# NoteIt.net
KiCad netlist of a schematic drawn in EAGLE
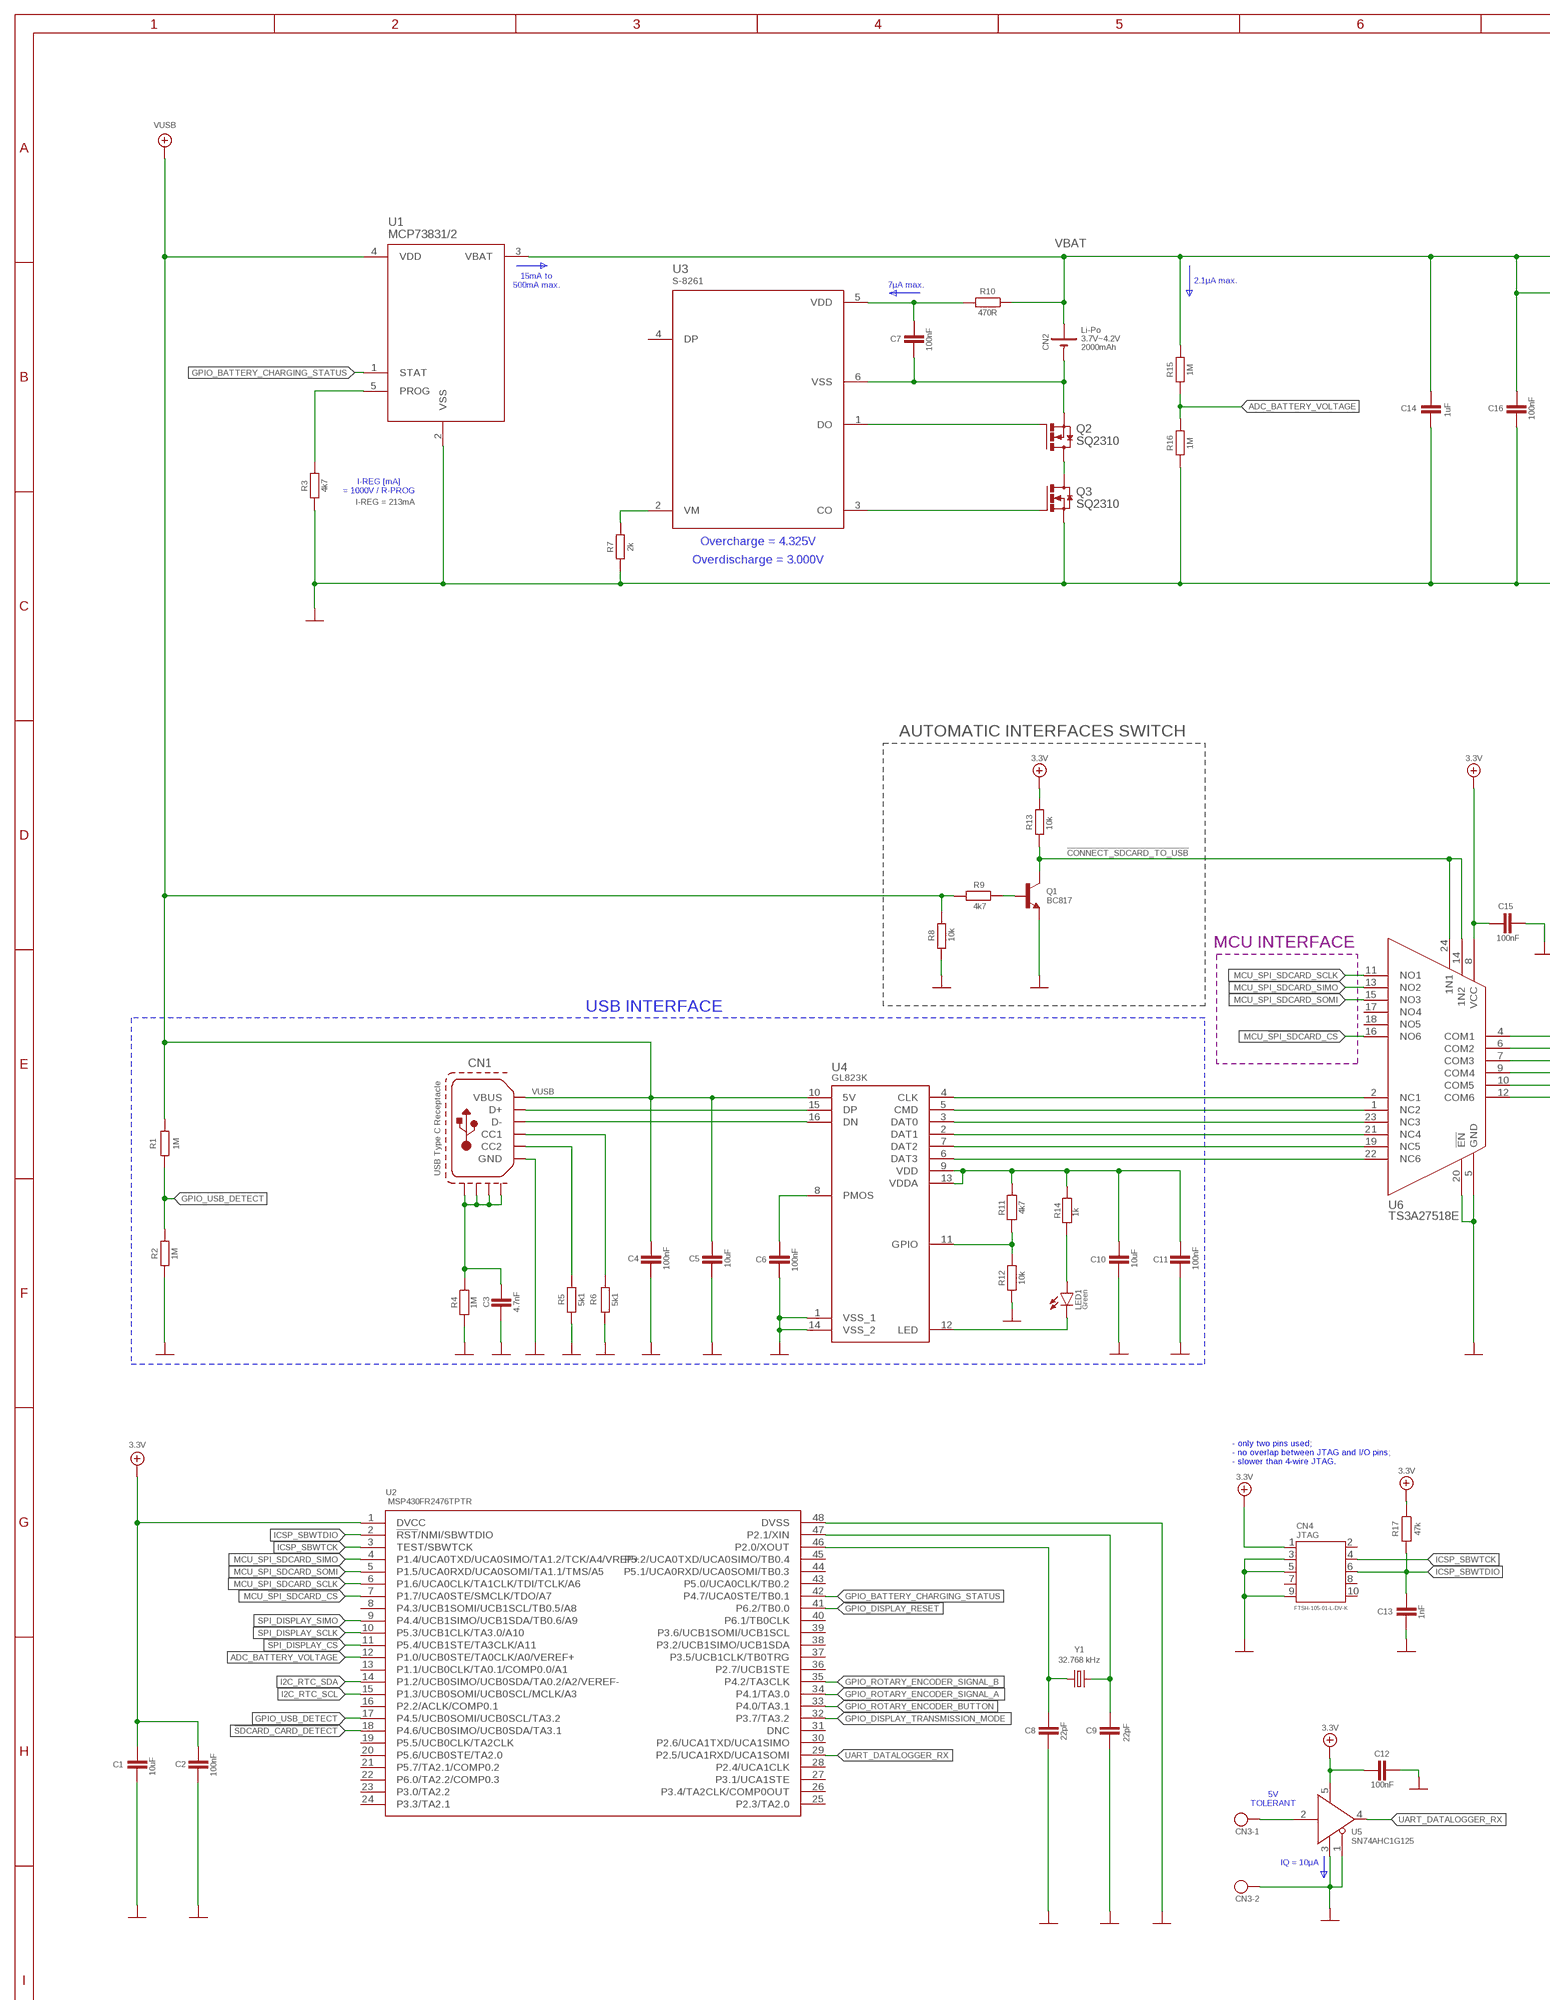
[diagram p0: schematic, sheet 1, part 1 of 2]
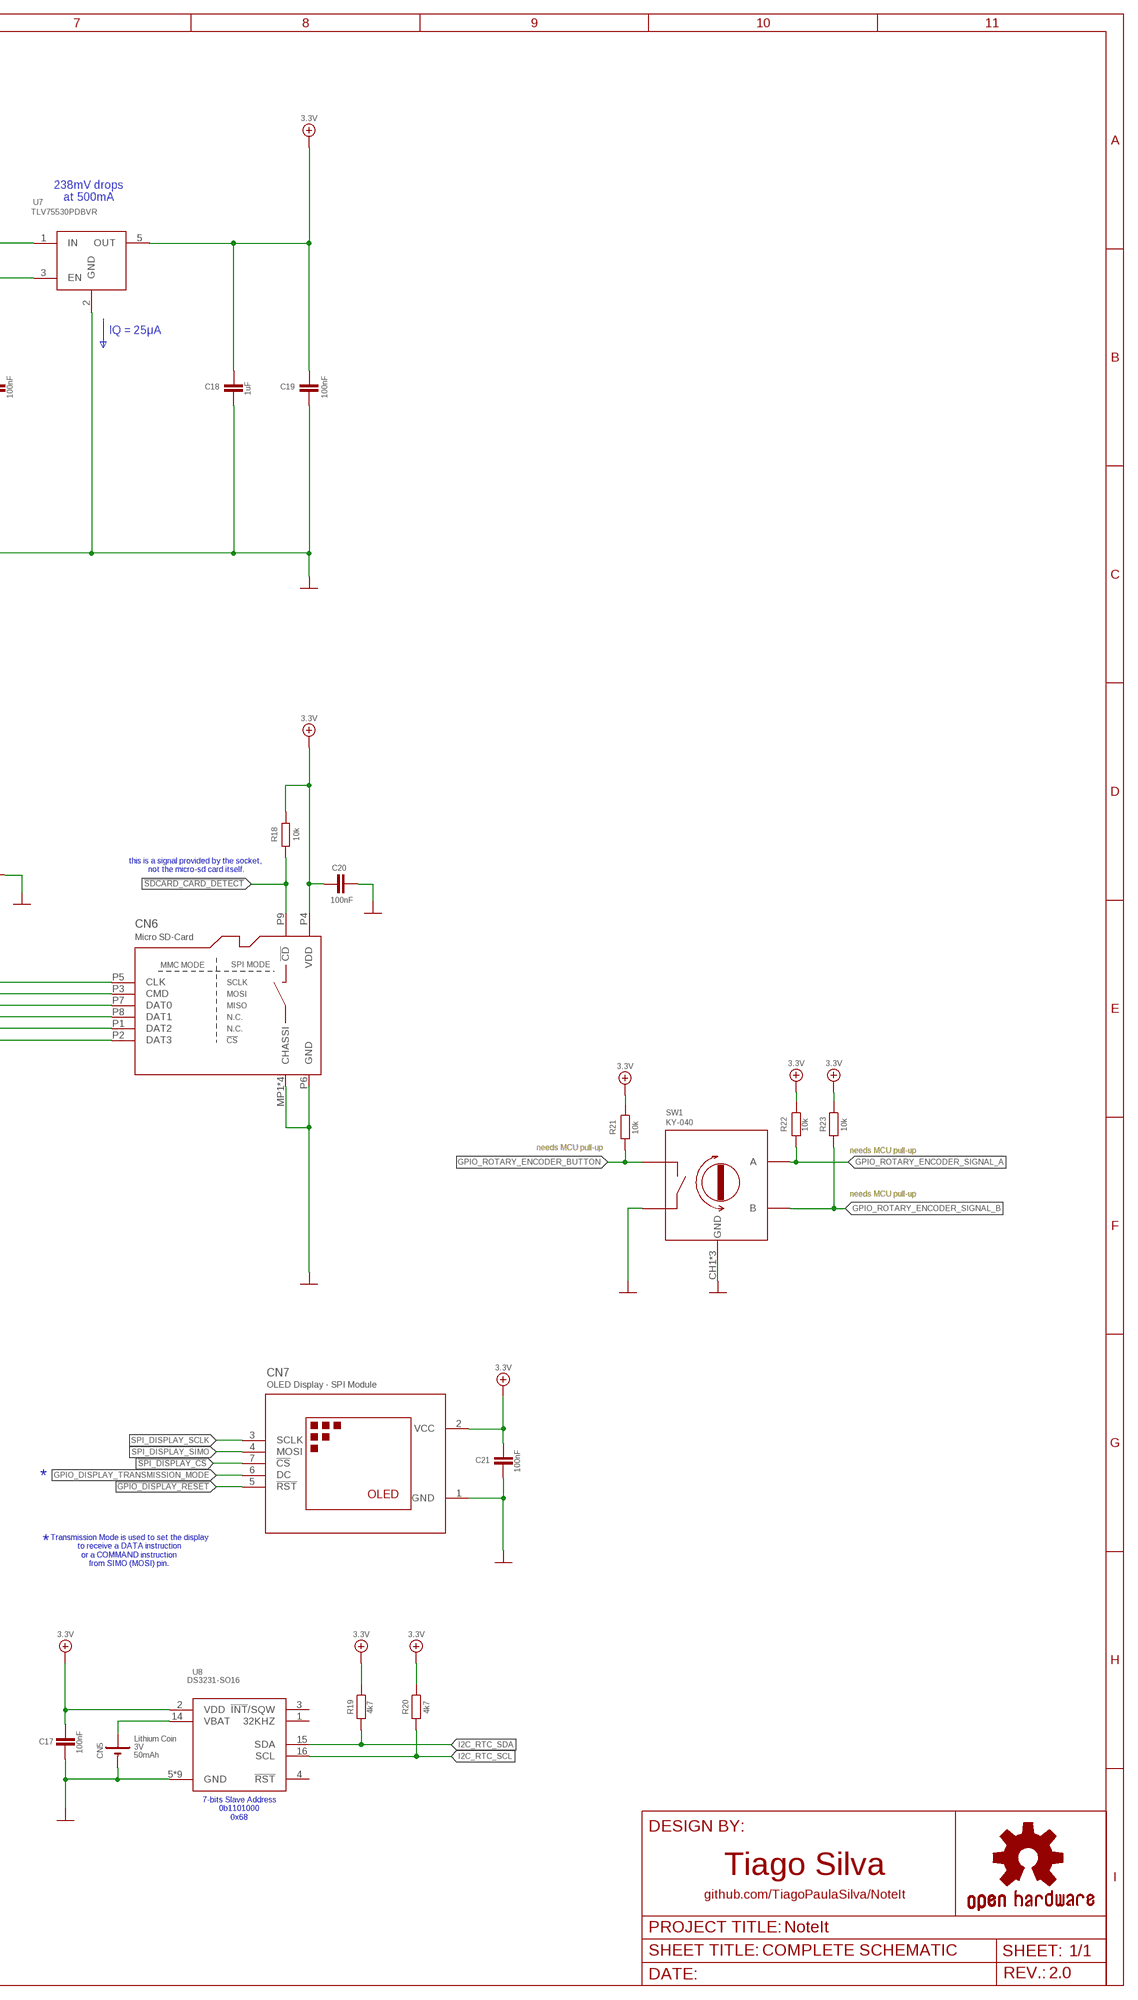
[diagram p1: schematic, sheet 1, part 2 of 2]

(export (version "E")
  (design (tool "Eeschema 10.0.6"))
  (components
    (comp (ref "C1")
      (value "10uF")
      (footprint "eagle-import:C0603")
      (libsource (lib "eagle-import") (part "C_0603"))
    )
    (comp (ref "C2")
      (value "100nF")
      (footprint "eagle-import:C0603")
      (libsource (lib "eagle-import") (part "C_0603"))
    )
    (comp (ref "C3")
      (value "4.7nF")
      (footprint "eagle-import:C0603")
      (libsource (lib "eagle-import") (part "C_0603"))
    )
    (comp (ref "C4")
      (value "100nF")
      (footprint "eagle-import:C0603")
      (libsource (lib "eagle-import") (part "C_0603"))
    )
    (comp (ref "C5")
      (value "10uF")
      (footprint "eagle-import:C0603")
      (libsource (lib "eagle-import") (part "C_0603"))
    )
    (comp (ref "C6")
      (value "100nF")
      (footprint "eagle-import:C0603")
      (libsource (lib "eagle-import") (part "C_0603"))
    )
    (comp (ref "C7")
      (value "100nF")
      (footprint "eagle-import:C0603")
      (libsource (lib "eagle-import") (part "C_0603"))
    )
    (comp (ref "C8")
      (value "22pF")
      (footprint "eagle-import:C0603")
      (libsource (lib "eagle-import") (part "C_0603"))
    )
    (comp (ref "C9")
      (value "22pF")
      (footprint "eagle-import:C0603")
      (libsource (lib "eagle-import") (part "C_0603"))
    )
    (comp (ref "C10")
      (value "10uF")
      (footprint "eagle-import:C0603")
      (libsource (lib "eagle-import") (part "C_0603"))
    )
    (comp (ref "C11")
      (value "100nF")
      (footprint "eagle-import:C0603")
      (libsource (lib "eagle-import") (part "C_0603"))
    )
    (comp (ref "C12")
      (value "100nF")
      (footprint "eagle-import:C0603")
      (libsource (lib "eagle-import") (part "C_0603"))
    )
    (comp (ref "C13")
      (value "1nF")
      (footprint "eagle-import:C0603")
      (libsource (lib "eagle-import") (part "C_0603"))
    )
    (comp (ref "C14")
      (value "1uF")
      (footprint "eagle-import:C0603")
      (libsource (lib "eagle-import") (part "C_0603"))
    )
    (comp (ref "C15")
      (value "100nF")
      (footprint "eagle-import:C0603")
      (libsource (lib "eagle-import") (part "C_0603"))
    )
    (comp (ref "C16")
      (value "100nF")
      (footprint "eagle-import:C0603")
      (libsource (lib "eagle-import") (part "C_0603"))
    )
    (comp (ref "C17")
      (value "100nF")
      (footprint "eagle-import:C0603")
      (libsource (lib "eagle-import") (part "C_0603"))
    )
    (comp (ref "C18")
      (value "1uF")
      (footprint "eagle-import:C0603")
      (libsource (lib "eagle-import") (part "C_0603"))
    )
    (comp (ref "C19")
      (value "100nF")
      (footprint "eagle-import:C0603")
      (libsource (lib "eagle-import") (part "C_0603"))
    )
    (comp (ref "C20")
      (value "100nF")
      (footprint "eagle-import:C0603")
      (libsource (lib "eagle-import") (part "C_0603"))
    )
    (comp (ref "C21")
      (value "100nF")
      (footprint "eagle-import:C0603")
      (libsource (lib "eagle-import") (part "C_0603"))
    )
    (comp (ref "CN1")
      (value "USB Type C Receptacle")
      (footprint "eagle-import:USB-C-16P-2LAYER-PADS")
      (libsource (lib "eagle-import") (part "USB-C-16P-2LAYERS"))
    )
    (comp (ref "CN2")
      (value "CELL-JST-PH-2P-H")
      (footprint "eagle-import:JST-PH-2P-H")
      (fields
        (field (name "CAPACITY") "2000mAh")
        (field (name "TYPE") "Li-Po")
        (field (name "VOLTAGE") "3.7V~4.2V")
      )
      (libsource (lib "eagle-import") (part "CELL-JST-PH-2P-H"))
    )
    (comp (ref "CN3")
      (value "2P-BLOCK-3.5MM-2P")
      (footprint "eagle-import:BLOCK-3.5MM-2P")
      (libsource (lib "eagle-import") (part "2P-BLOCK-3.5MM-2P"))
    )
    (comp (ref "CN4")
      (value "JTAG")
      (footprint "eagle-import:JTAG-ARM-10P")
      (fields (field (name "PN") "FTSH-105-01-L-DV-K"))
      (libsource (lib "eagle-import") (part "JTAG"))
    )
    (comp (ref "CN5")
      (value "CR-1225")
      (footprint "eagle-import:CR1220_1225_HOLDER")
      (fields
        (field (name "TYPE") "Lithium Coin")
        (field (name "VOLTAGE") "3V")
        (field (name "CAPACITY") "50mAh")
      )
      (libsource (lib "eagle-import") (part "CR-1225"))
    )
    (comp (ref "CN6")
      (value "Micro SD-Card")
      (footprint "eagle-import:SD-CARD")
      (libsource (lib "eagle-import") (part "SD-CARD"))
    )
    (comp (ref "CN7")
      (value "OLED-MODULE-SPI-NO_HOLES")
      (footprint "eagle-import:PIN_HEADER_1X7_NH")
      (fields (field (name "FAMILY") "OLED Display - SPI Module"))
      (libsource (lib "eagle-import") (part "OLED-MODULE-SPI-NO_HOLES"))
    )
    (comp (ref "LED1")
      (value "LED-0603")
      (footprint "eagle-import:LED-0603")
      (fields (field (name "FAMILY") "Green"))
      (libsource (lib "eagle-import") (part "LED-0603"))
    )
    (comp (ref "Q1")
      (value "BC817")
      (footprint "eagle-import:SOT23-3")
      (libsource (lib "eagle-import") (part "NPN-BC817"))
    )
    (comp (ref "Q2")
      (value "N-FET-ENHANCEMENT-SQ2310")
      (footprint "eagle-import:SOT23-3")
      (fields (field (name "FAMILY") "SQ2310"))
      (libsource (lib "eagle-import") (part "N-FET-ENHANCEMENT-SQ2310"))
    )
    (comp (ref "Q3")
      (value "N-FET-ENHANCEMENT-SQ2310")
      (footprint "eagle-import:SOT23-3")
      (fields (field (name "FAMILY") "SQ2310"))
      (libsource (lib "eagle-import") (part "N-FET-ENHANCEMENT-SQ2310"))
    )
    (comp (ref "R1")
      (value "1M")
      (footprint "eagle-import:R0603")
      (libsource (lib "eagle-import") (part "R_0603"))
    )
    (comp (ref "R2")
      (value "1M")
      (footprint "eagle-import:R0603")
      (libsource (lib "eagle-import") (part "R_0603"))
    )
    (comp (ref "R3")
      (value "4k7")
      (footprint "eagle-import:R0603")
      (libsource (lib "eagle-import") (part "R_0603"))
    )
    (comp (ref "R4")
      (value "1M")
      (footprint "eagle-import:R0603")
      (libsource (lib "eagle-import") (part "R_0603"))
    )
    (comp (ref "R5")
      (value "5k1")
      (footprint "eagle-import:R0603")
      (libsource (lib "eagle-import") (part "R_0603"))
    )
    (comp (ref "R6")
      (value "5k1")
      (footprint "eagle-import:R0603")
      (libsource (lib "eagle-import") (part "R_0603"))
    )
    (comp (ref "R7")
      (value "2k")
      (footprint "eagle-import:R0603")
      (libsource (lib "eagle-import") (part "R_0603"))
    )
    (comp (ref "R8")
      (value "10k")
      (footprint "eagle-import:R0603")
      (libsource (lib "eagle-import") (part "R_0603"))
    )
    (comp (ref "R9")
      (value "4k7")
      (footprint "eagle-import:R0603")
      (libsource (lib "eagle-import") (part "R_0603"))
    )
    (comp (ref "R10")
      (value "470R")
      (footprint "eagle-import:R0603")
      (libsource (lib "eagle-import") (part "R_0603"))
    )
    (comp (ref "R11")
      (value "4k7")
      (footprint "eagle-import:R0603")
      (libsource (lib "eagle-import") (part "R_0603"))
    )
    (comp (ref "R12")
      (value "10k")
      (footprint "eagle-import:R0603")
      (libsource (lib "eagle-import") (part "R_0603"))
    )
    (comp (ref "R13")
      (value "10k")
      (footprint "eagle-import:R0603")
      (libsource (lib "eagle-import") (part "R_0603"))
    )
    (comp (ref "R14")
      (value "1k")
      (footprint "eagle-import:R0603")
      (libsource (lib "eagle-import") (part "R_0603"))
    )
    (comp (ref "R15")
      (value "1M")
      (footprint "eagle-import:R0603")
      (libsource (lib "eagle-import") (part "R_0603"))
    )
    (comp (ref "R16")
      (value "1M")
      (footprint "eagle-import:R0603")
      (libsource (lib "eagle-import") (part "R_0603"))
    )
    (comp (ref "R17")
      (value "47k")
      (footprint "eagle-import:R0603")
      (libsource (lib "eagle-import") (part "R_0603"))
    )
    (comp (ref "R18")
      (value "10k")
      (footprint "eagle-import:R0603")
      (libsource (lib "eagle-import") (part "R_0603"))
    )
    (comp (ref "R19")
      (value "4k7")
      (footprint "eagle-import:R0603")
      (libsource (lib "eagle-import") (part "R_0603"))
    )
    (comp (ref "R20")
      (value "4k7")
      (footprint "eagle-import:R0603")
      (libsource (lib "eagle-import") (part "R_0603"))
    )
    (comp (ref "R21")
      (value "10k")
      (footprint "eagle-import:R0603")
      (libsource (lib "eagle-import") (part "R_0603"))
    )
    (comp (ref "R22")
      (value "10k")
      (footprint "eagle-import:R0603")
      (libsource (lib "eagle-import") (part "R_0603"))
    )
    (comp (ref "R23")
      (value "10k")
      (footprint "eagle-import:R0603")
      (libsource (lib "eagle-import") (part "R_0603"))
    )
    (comp (ref "SW1")
      (value "KY-040")
      (footprint "eagle-import:KY-040")
      (libsource (lib "eagle-import") (part "ROTARY-ENCODER"))
    )
    (comp (ref "U1")
      (value "MCP73831/2")
      (footprint "eagle-import:SOT-23-5")
      (libsource (lib "eagle-import") (part "MCP73831T-2ACI/OT"))
    )
    (comp (ref "U2")
      (value "MSP430FR2476TPTR")
      (footprint "eagle-import:LQFP-48")
      (fields
        (field (name "MOUSER_PART_NUMBER") "595-MSP430FR2476TPTR")
        (field (name "PN") "MSP430FR2476TPTR")
      )
      (libsource (lib "eagle-import") (part "MSP430FR2476TPTR"))
    )
    (comp (ref "U3")
      (value "S-8261")
      (footprint "eagle-import:SOT-23-6")
      (fields (field (name "SPICEPREFIX") "X"))
      (libsource (lib "eagle-import") (part "S-8261"))
    )
    (comp (ref "U4")
      (value "GL823K")
      (footprint "eagle-import:SSOP16")
      (libsource (lib "eagle-import") (part "GL823K"))
    )
    (comp (ref "U5")
      (value "SN74AHC1G125")
      (footprint "eagle-import:SOT-23-5")
      (libsource (lib "eagle-import") (part "SN74AHC1G125"))
    )
    (comp (ref "U6")
      (value "TS3A27518E")
      (footprint "eagle-import:TSSOP-24")
      (libsource (lib "eagle-import") (part "TS3A27518E"))
    )
    (comp (ref "U7")
      (value "TLV75530PDBVR")
      (footprint "eagle-import:SOT-23-5")
      (libsource (lib "eagle-import") (part "TLV75530PDBVR"))
    )
    (comp (ref "U8")
      (value "DS3231-SO16")
      (footprint "eagle-import:SOIC-16W_(SO16)")
      (libsource (lib "eagle-import") (part "DS3231-SO16"))
    )
    (comp (ref "Y1")
      (value "32.768 kHz")
      (footprint "eagle-import:3.2MM_1.6MM")
      (fields (field (name "PN") "CM7V-T1A-32.768k-9pF-20PPM-TA-QA T3"))
      (libsource (lib "eagle-import") (part "OSC-32.768KHZ"))
    )
  )
  (nets
    (net (code "1") (name "/MCU_~{SPI_SDCARD_CS}") (class "Default")
      (node (ref "U2") (pin "7") (pinfunction "P1.7/UCA0STE/SMCLK/TDO/A7_7") (pintype "bidirectional"))
      (node (ref "U6") (pin "16") (pinfunction "NO6_16") (pintype "bidirectional"))
    )
    (net (code "2") (name "/VBAT") (class "Default")
      (node (ref "C14") (pin "1") (pinfunction "1_1") (pintype "passive"))
      (node (ref "C16") (pin "1") (pinfunction "1_1") (pintype "passive"))
      (node (ref "CN2") (pin "1") (pinfunction "+_1") (pintype "passive"))
      (node (ref "R10") (pin "1") (pinfunction "1_1") (pintype "passive"))
      (node (ref "R15") (pin "2") (pinfunction "2_2") (pintype "passive"))
      (node (ref "U1") (pin "3") (pinfunction "VBAT_3") (pintype "bidirectional"))
      (node (ref "U7") (pin "1") (pinfunction "IN_1") (pintype "bidirectional"))
      (node (ref "U7") (pin "3") (pinfunction "EN_3") (pintype "bidirectional"))
    )
    (net (code "3") (name "/~{CONNECT_SDCARD_TO_USB}") (class "Default")
      (node (ref "Q1") (pin "3") (pinfunction "C_3") (pintype "passive"))
      (node (ref "R13") (pin "1") (pinfunction "1_1") (pintype "passive"))
      (node (ref "U6") (pin "14") (pinfunction "1N2_14") (pintype "input"))
      (node (ref "U6") (pin "24") (pinfunction "1N1_24") (pintype "input"))
    )
    (net (code "4") (name "/~{GPIO_DISPLAY_RESET}") (class "Default")
      (node (ref "CN7") (pin "5") (pinfunction "~{RST}_5") (pintype "bidirectional"))
      (node (ref "U2") (pin "41") (pinfunction "P6.2/TB0.0_41") (pintype "bidirectional"))
    )
    (net (code "5") (name "/~{SDCARD_CARD_DETECT}") (class "Default")
      (node (ref "CN6") (pin "P9") (pinfunction "~{CD}_P9") (pintype "bidirectional"))
      (node (ref "R18") (pin "2") (pinfunction "2_2") (pintype "passive"))
      (node (ref "U2") (pin "18") (pinfunction "P4.6/UCB0SIMO/UCB0SDA/TA3.1_18") (pintype "bidirectional"))
    )
    (net (code "6") (name "/~{SPI_DISPLAY_CS}") (class "Default")
      (node (ref "CN7") (pin "7") (pinfunction "~{CS}_7") (pintype "bidirectional"))
      (node (ref "U2") (pin "11") (pinfunction "P5.4/UCB1STE/TA3CLK/A11_11") (pintype "bidirectional"))
    )
    (net (code "7") (name "0V") (class "Default")
      (node (ref "C1") (pin "2") (pinfunction "2_2") (pintype "passive"))
      (node (ref "C10") (pin "1") (pinfunction "1_1") (pintype "passive"))
      (node (ref "C11") (pin "1") (pinfunction "1_1") (pintype "passive"))
      (node (ref "C12") (pin "2") (pinfunction "2_2") (pintype "passive"))
      (node (ref "C13") (pin "2") (pinfunction "2_2") (pintype "passive"))
      (node (ref "C14") (pin "2") (pinfunction "2_2") (pintype "passive"))
      (node (ref "C15") (pin "1") (pinfunction "1_1") (pintype "passive"))
      (node (ref "C16") (pin "2") (pinfunction "2_2") (pintype "passive"))
      (node (ref "C17") (pin "1") (pinfunction "1_1") (pintype "passive"))
      (node (ref "C18") (pin "2") (pinfunction "2_2") (pintype "passive"))
      (node (ref "C19") (pin "2") (pinfunction "2_2") (pintype "passive"))
      (node (ref "C2") (pin "2") (pinfunction "2_2") (pintype "passive"))
      (node (ref "C20") (pin "1") (pinfunction "1_1") (pintype "passive"))
      (node (ref "C21") (pin "2") (pinfunction "2_2") (pintype "passive"))
      (node (ref "C3") (pin "1") (pinfunction "1_1") (pintype "passive"))
      (node (ref "C4") (pin "1") (pinfunction "1_1") (pintype "passive"))
      (node (ref "C5") (pin "1") (pinfunction "1_1") (pintype "passive"))
      (node (ref "C6") (pin "1") (pinfunction "1_1") (pintype "passive"))
      (node (ref "C8") (pin "2") (pinfunction "2_2") (pintype "passive"))
      (node (ref "C9") (pin "2") (pinfunction "2_2") (pintype "passive"))
      (node (ref "CN1") (pin "GND") (pinfunction "GND_GND") (pintype "bidirectional"))
      (node (ref "CN1") (pin "GND2") (pinfunction "GND_GND2") (pintype "bidirectional"))
      (node (ref "CN3") (pin "2") (pinfunction "P$1_2") (pintype "passive"))
      (node (ref "CN4") (pin "3") (pinfunction "GND_3") (pintype "bidirectional"))
      (node (ref "CN4") (pin "5") (pinfunction "GND2_5") (pintype "bidirectional"))
      (node (ref "CN4") (pin "9") (pinfunction "GND3_9") (pintype "bidirectional"))
      (node (ref "CN5") (pin "-") (pinfunction "-_-") (pintype "passive"))
      (node (ref "CN6") (pin "MP1") (pinfunction "CHASSI_MP1") (pintype "bidirectional"))
      (node (ref "CN6") (pin "MP2") (pinfunction "CHASSI_MP2") (pintype "bidirectional"))
      (node (ref "CN6") (pin "MP3") (pinfunction "CHASSI_MP3") (pintype "bidirectional"))
      (node (ref "CN6") (pin "MP4") (pinfunction "CHASSI_MP4") (pintype "bidirectional"))
      (node (ref "CN6") (pin "P6") (pinfunction "GND_P6") (pintype "bidirectional"))
      (node (ref "CN7") (pin "1") (pinfunction "GND_1") (pintype "power_in"))
      (node (ref "Q1") (pin "2") (pinfunction "E_2") (pintype "passive"))
      (node (ref "Q3") (pin "2") (pinfunction "S_2") (pintype "passive"))
      (node (ref "R12") (pin "1") (pinfunction "1_1") (pintype "passive"))
      (node (ref "R16") (pin "1") (pinfunction "1_1") (pintype "passive"))
      (node (ref "R2") (pin "1") (pinfunction "1_1") (pintype "passive"))
      (node (ref "R3") (pin "1") (pinfunction "1_1") (pintype "passive"))
      (node (ref "R4") (pin "2") (pinfunction "2_2") (pintype "passive"))
      (node (ref "R5") (pin "2") (pinfunction "2_2") (pintype "passive"))
      (node (ref "R6") (pin "2") (pinfunction "2_2") (pintype "passive"))
      (node (ref "R7") (pin "1") (pinfunction "1_1") (pintype "passive"))
      (node (ref "R8") (pin "2") (pinfunction "2_2") (pintype "passive"))
      (node (ref "SW1") (pin "CH1") (pinfunction "GND_CH1") (pintype "power_in"))
      (node (ref "SW1") (pin "CH2") (pinfunction "GND_CH2") (pintype "power_in"))
      (node (ref "SW1") (pin "GND") (pinfunction "GND_GND") (pintype "power_in"))
      (node (ref "SW1") (pin "SW2") (pinfunction "SW2_SW2") (pintype "power_in"))
      (node (ref "U1") (pin "2") (pinfunction "VSS_2") (pintype "power_in"))
      (node (ref "U2") (pin "48") (pinfunction "DVSS_48") (pintype "bidirectional"))
      (node (ref "U4") (pin "1") (pinfunction "VSS_1_1") (pintype "bidirectional"))
      (node (ref "U4") (pin "14") (pinfunction "VSS_2_14") (pintype "bidirectional"))
      (node (ref "U5") (pin "1") (pinfunction "~{OE}_1") (pintype "bidirectional"))
      (node (ref "U5") (pin "3") (pinfunction "GND_3") (pintype "bidirectional"))
      (node (ref "U6") (pin "20") (pinfunction "~{EN}_20") (pintype "input"))
      (node (ref "U6") (pin "5") (pinfunction "GND_5") (pintype "power_in"))
      (node (ref "U7") (pin "2") (pinfunction "GND_2") (pintype "bidirectional"))
      (node (ref "U8") (pin "10") (pinfunction "GND_10") (pintype "power_in"))
      (node (ref "U8") (pin "11") (pinfunction "GND_11") (pintype "power_in"))
      (node (ref "U8") (pin "12") (pinfunction "GND_12") (pintype "power_in"))
      (node (ref "U8") (pin "13") (pinfunction "GND_13") (pintype "power_in"))
      (node (ref "U8") (pin "5") (pinfunction "GND_5") (pintype "power_in"))
      (node (ref "U8") (pin "6") (pinfunction "GND_6") (pintype "power_in"))
      (node (ref "U8") (pin "7") (pinfunction "GND_7") (pintype "power_in"))
      (node (ref "U8") (pin "8") (pinfunction "GND_8") (pintype "power_in"))
      (node (ref "U8") (pin "9") (pinfunction "GND_9") (pintype "power_in"))
    )
    (net (code "8") (name "3.3V") (class "Default")
      (node (ref "C1") (pin "1") (pinfunction "1_1") (pintype "passive"))
      (node (ref "C12") (pin "1") (pinfunction "1_1") (pintype "passive"))
      (node (ref "C15") (pin "2") (pinfunction "2_2") (pintype "passive"))
      (node (ref "C17") (pin "2") (pinfunction "2_2") (pintype "passive"))
      (node (ref "C18") (pin "1") (pinfunction "1_1") (pintype "passive"))
      (node (ref "C19") (pin "1") (pinfunction "1_1") (pintype "passive"))
      (node (ref "C2") (pin "1") (pinfunction "1_1") (pintype "passive"))
      (node (ref "C20") (pin "2") (pinfunction "2_2") (pintype "passive"))
      (node (ref "C21") (pin "1") (pinfunction "1_1") (pintype "passive"))
      (node (ref "CN4") (pin "1") (pinfunction "VDD_1") (pintype "bidirectional"))
      (node (ref "CN6") (pin "P4") (pinfunction "VDD_P4") (pintype "bidirectional"))
      (node (ref "CN7") (pin "2") (pinfunction "VCC_2") (pintype "power_in"))
      (node (ref "R13") (pin "2") (pinfunction "2_2") (pintype "passive"))
      (node (ref "R17") (pin "1") (pinfunction "1_1") (pintype "passive"))
      (node (ref "R18") (pin "1") (pinfunction "1_1") (pintype "passive"))
      (node (ref "R19") (pin "1") (pinfunction "1_1") (pintype "passive"))
      (node (ref "R20") (pin "1") (pinfunction "1_1") (pintype "passive"))
      (node (ref "R21") (pin "1") (pinfunction "1_1") (pintype "passive"))
      (node (ref "R22") (pin "1") (pinfunction "1_1") (pintype "passive"))
      (node (ref "R23") (pin "1") (pinfunction "1_1") (pintype "passive"))
      (node (ref "U2") (pin "1") (pinfunction "DVCC_1") (pintype "bidirectional"))
      (node (ref "U5") (pin "5") (pinfunction "VDD_5") (pintype "bidirectional"))
      (node (ref "U6") (pin "8") (pinfunction "VCC_8") (pintype "power_in"))
      (node (ref "U7") (pin "5") (pinfunction "OUT_5") (pintype "bidirectional"))
      (node (ref "U8") (pin "2") (pinfunction "VDD_2") (pintype "power_in"))
    )
    (net (code "9") (name "ADC_BATTERY_VOLTAGE") (class "Default")
      (node (ref "R15") (pin "1") (pinfunction "1_1") (pintype "passive"))
      (node (ref "R16") (pin "2") (pinfunction "2_2") (pintype "passive"))
      (node (ref "U2") (pin "12") (pinfunction "P1.0/UCB0STE/TA0CLK/A0/VEREF+_12") (pintype "bidirectional"))
    )
    (net (code "10") (name "GPIO_BATTERY_CHARGING_STATUS") (class "Default")
      (node (ref "U1") (pin "1") (pinfunction "STAT_1") (pintype "output"))
      (node (ref "U2") (pin "42") (pinfunction "P4.7/UCA0STE/TB0.1_42") (pintype "bidirectional"))
    )
    (net (code "11") (name "GPIO_DISPLAY_TRANSMISSION_MODE") (class "Default")
      (node (ref "CN7") (pin "6") (pinfunction "DC_6") (pintype "bidirectional"))
      (node (ref "U2") (pin "32") (pinfunction "P3.7/TA3.2_32") (pintype "bidirectional"))
    )
    (net (code "12") (name "GPIO_ROTARY_ENCODER_BUTTON") (class "Default")
      (node (ref "R21") (pin "2") (pinfunction "2_2") (pintype "passive"))
      (node (ref "SW1") (pin "SW1") (pinfunction "SW1_SW1") (pintype "bidirectional"))
      (node (ref "U2") (pin "33") (pinfunction "P4.0/TA3.1_33") (pintype "bidirectional"))
    )
    (net (code "13") (name "GPIO_ROTARY_ENCODER_SIGNAL_A") (class "Default")
      (node (ref "R22") (pin "2") (pinfunction "2_2") (pintype "passive"))
      (node (ref "SW1") (pin "A") (pinfunction "A_A") (pintype "bidirectional"))
      (node (ref "U2") (pin "34") (pinfunction "P4.1/TA3.0_34") (pintype "bidirectional"))
    )
    (net (code "14") (name "GPIO_ROTARY_ENCODER_SIGNAL_B") (class "Default")
      (node (ref "R23") (pin "2") (pinfunction "2_2") (pintype "passive"))
      (node (ref "SW1") (pin "B") (pinfunction "B_B") (pintype "bidirectional"))
      (node (ref "U2") (pin "35") (pinfunction "P4.2/TA3CLK_35") (pintype "bidirectional"))
    )
    (net (code "15") (name "GPIO_USB_DETECT") (class "Default")
      (node (ref "R1") (pin "1") (pinfunction "1_1") (pintype "passive"))
      (node (ref "R2") (pin "2") (pinfunction "2_2") (pintype "passive"))
      (node (ref "U2") (pin "17") (pinfunction "P4.5/UCB0SOMI/UCB0SCL/TA3.2_17") (pintype "bidirectional"))
    )
    (net (code "16") (name "I2C_RTC_SCL") (class "Default")
      (node (ref "R20") (pin "2") (pinfunction "2_2") (pintype "passive"))
      (node (ref "U2") (pin "15") (pinfunction "P1.3/UCB0SOMI/UCB0SCL/MCLK/A3_15") (pintype "bidirectional"))
      (node (ref "U8") (pin "16") (pinfunction "SCL_16") (pintype "bidirectional"))
    )
    (net (code "17") (name "I2C_RTC_SDA") (class "Default")
      (node (ref "R19") (pin "2") (pinfunction "2_2") (pintype "passive"))
      (node (ref "U2") (pin "14") (pinfunction "P1.2/UCB0SIMO/UCB0SDA/TA0.2/A2/VEREF-_14") (pintype "bidirectional"))
      (node (ref "U8") (pin "15") (pinfunction "SDA_15") (pintype "bidirectional"))
    )
    (net (code "18") (name "ICSP_SBWTCK") (class "Default")
      (node (ref "CN4") (pin "4") (pinfunction "TCK_4") (pintype "bidirectional"))
      (node (ref "U2") (pin "3") (pinfunction "TEST/SBWTCK_3") (pintype "bidirectional"))
    )
    (net (code "19") (name "ICSP_SBWTDIO") (class "Default")
      (node (ref "C13") (pin "1") (pinfunction "1_1") (pintype "passive"))
      (node (ref "CN4") (pin "6") (pinfunction "TDO_6") (pintype "bidirectional"))
      (node (ref "R17") (pin "2") (pinfunction "2_2") (pintype "passive"))
      (node (ref "U2") (pin "2") (pinfunction "~{RST}/NMI/SBWTDIO_2") (pintype "bidirectional"))
    )
    (net (code "20") (name "MCU_SPI_SDCARD_SCLK") (class "Default")
      (node (ref "U2") (pin "6") (pinfunction "P1.6/UCA0CLK/TA1CLK/TDI/TCLK/A6_6") (pintype "bidirectional"))
      (node (ref "U6") (pin "11") (pinfunction "NO1_11") (pintype "bidirectional"))
    )
    (net (code "21") (name "MCU_SPI_SDCARD_SIMO") (class "Default")
      (node (ref "U2") (pin "4") (pinfunction "P1.4/UCA0TXD/UCA0SIMO/TA1.2/TCK/A4/VREF+_4") (pintype "bidirectional"))
      (node (ref "U6") (pin "13") (pinfunction "NO2_13") (pintype "bidirectional"))
    )
    (net (code "22") (name "MCU_SPI_SDCARD_SOMI") (class "Default")
      (node (ref "U2") (pin "5") (pinfunction "P1.5/UCA0RXD/UCA0SOMI/TA1.1/TMS/A5_5") (pintype "bidirectional"))
      (node (ref "U6") (pin "15") (pinfunction "NO3_15") (pintype "bidirectional"))
    )
    (net (code "23") (name "Net-(CN1-CC1)") (class "Default")
      (node (ref "CN1") (pin "A5") (pinfunction "CC1_A5") (pintype "bidirectional"))
      (node (ref "R6") (pin "1") (pinfunction "1_1") (pintype "passive"))
    )
    (net (code "24") (name "Net-(CN1-CC2)") (class "Default")
      (node (ref "CN1") (pin "B5") (pinfunction "CC2_B5") (pintype "bidirectional"))
      (node (ref "R5") (pin "1") (pinfunction "1_1") (pintype "passive"))
    )
    (net (code "25") (name "Net-(CN1-S1)") (class "Default")
      (node (ref "C3") (pin "2") (pinfunction "2_2") (pintype "passive"))
      (node (ref "CN1") (pin "SHLD1") (pinfunction "S1_SHLD1") (pintype "passive"))
      (node (ref "CN1") (pin "SHLD2") (pinfunction "S2_SHLD2") (pintype "passive"))
      (node (ref "CN1") (pin "SHLD3") (pinfunction "S3_SHLD3") (pintype "passive"))
      (node (ref "CN1") (pin "SHLD4") (pinfunction "S4_SHLD4") (pintype "passive"))
      (node (ref "R4") (pin "1") (pinfunction "1_1") (pintype "passive"))
    )
    (net (code "26") (name "Net-(CN2--)") (class "Default")
      (node (ref "C7") (pin "2") (pinfunction "2_2") (pintype "passive"))
      (node (ref "CN2") (pin "2") (pinfunction "-_2") (pintype "passive"))
      (node (ref "Q2") (pin "2") (pinfunction "S_2") (pintype "passive"))
      (node (ref "U3") (pin "6") (pinfunction "VSS_6") (pintype "bidirectional"))
    )
    (net (code "27") (name "Net-(CN3A-P$1)") (class "Default")
      (node (ref "CN3") (pin "1") (pinfunction "P$1_1") (pintype "passive"))
      (node (ref "U5") (pin "2") (pinfunction "IN_2") (pintype "bidirectional"))
    )
    (net (code "28") (name "Net-(CN6-CLK)") (class "Default")
      (node (ref "CN6") (pin "P5") (pinfunction "CLK_P5") (pintype "bidirectional"))
      (node (ref "U6") (pin "4") (pinfunction "COM1_4") (pintype "bidirectional"))
    )
    (net (code "29") (name "Net-(CN6-CMD)") (class "Default")
      (node (ref "CN6") (pin "P3") (pinfunction "CMD_P3") (pintype "bidirectional"))
      (node (ref "U6") (pin "6") (pinfunction "COM2_6") (pintype "bidirectional"))
    )
    (net (code "30") (name "Net-(CN6-DAT0)") (class "Default")
      (node (ref "CN6") (pin "P7") (pinfunction "DAT0_P7") (pintype "bidirectional"))
      (node (ref "U6") (pin "7") (pinfunction "COM3_7") (pintype "bidirectional"))
    )
    (net (code "31") (name "Net-(CN6-DAT1)") (class "Default")
      (node (ref "CN6") (pin "P8") (pinfunction "DAT1_P8") (pintype "bidirectional"))
      (node (ref "U6") (pin "9") (pinfunction "COM4_9") (pintype "bidirectional"))
    )
    (net (code "32") (name "Net-(CN6-DAT2)") (class "Default")
      (node (ref "CN6") (pin "P1") (pinfunction "DAT2_P1") (pintype "bidirectional"))
      (node (ref "U6") (pin "10") (pinfunction "COM5_10") (pintype "bidirectional"))
    )
    (net (code "33") (name "Net-(CN6-DAT3)") (class "Default")
      (node (ref "CN6") (pin "P2") (pinfunction "DAT3_P2") (pintype "bidirectional"))
      (node (ref "U6") (pin "12") (pinfunction "COM6_12") (pintype "bidirectional"))
    )
    (net (code "34") (name "Net-(LED1-K)") (class "Default")
      (node (ref "LED1") (pin "C") (pinfunction "K_C") (pintype "passive"))
      (node (ref "U4") (pin "12") (pinfunction "LED_12") (pintype "bidirectional"))
    )
    (net (code "35") (name "Net-(LED1-PadA)") (class "Default")
      (node (ref "LED1") (pin "A") (pinfunction "A_A") (pintype "passive"))
      (node (ref "R14") (pin "2") (pinfunction "2_2") (pintype "passive"))
    )
    (net (code "36") (name "Net-(Q1-B)") (class "Default")
      (node (ref "Q1") (pin "1") (pinfunction "B_1") (pintype "passive"))
      (node (ref "R9") (pin "1") (pinfunction "1_1") (pintype "passive"))
    )
    (net (code "37") (name "Net-(Q2-D)") (class "Default")
      (node (ref "Q2") (pin "3") (pinfunction "D_3") (pintype "passive"))
      (node (ref "Q3") (pin "3") (pinfunction "D_3") (pintype "passive"))
    )
    (net (code "38") (name "Net-(Q2-G)") (class "Default")
      (node (ref "Q2") (pin "1") (pinfunction "G_1") (pintype "passive"))
      (node (ref "U3") (pin "1") (pinfunction "DO_1") (pintype "bidirectional"))
    )
    (net (code "39") (name "Net-(Q3-G)") (class "Default")
      (node (ref "Q3") (pin "1") (pinfunction "G_1") (pintype "passive"))
      (node (ref "U3") (pin "3") (pinfunction "CO_3") (pintype "bidirectional"))
    )
    (net (code "40") (name "Net-(U1-PROG)") (class "Default")
      (node (ref "R3") (pin "2") (pinfunction "2_2") (pintype "passive"))
      (node (ref "U1") (pin "5") (pinfunction "PROG_5") (pintype "input"))
    )
    (net (code "41") (name "Net-(U2-P2.0{slash}XOUT)") (class "Default")
      (node (ref "C8") (pin "1") (pinfunction "1_1") (pintype "passive"))
      (node (ref "U2") (pin "46") (pinfunction "P2.0/XOUT_46") (pintype "bidirectional"))
      (node (ref "Y1") (pin "1") (pinfunction "1_1") (pintype "passive"))
    )
    (net (code "42") (name "Net-(U2-P2.1{slash}XIN)") (class "Default")
      (node (ref "C9") (pin "1") (pinfunction "1_1") (pintype "passive"))
      (node (ref "U2") (pin "47") (pinfunction "P2.1/XIN_47") (pintype "bidirectional"))
      (node (ref "Y1") (pin "2") (pinfunction "2_2") (pintype "passive"))
    )
    (net (code "43") (name "Net-(U3-VDD)") (class "Default")
      (node (ref "C7") (pin "1") (pinfunction "1_1") (pintype "passive"))
      (node (ref "R10") (pin "2") (pinfunction "2_2") (pintype "passive"))
      (node (ref "U3") (pin "5") (pinfunction "VDD_5") (pintype "bidirectional"))
    )
    (net (code "44") (name "Net-(U3-VM)") (class "Default")
      (node (ref "R7") (pin "2") (pinfunction "2_2") (pintype "passive"))
      (node (ref "U3") (pin "2") (pinfunction "VM_2") (pintype "bidirectional"))
    )
    (net (code "45") (name "Net-(U4-CLK)") (class "Default")
      (node (ref "U4") (pin "4") (pinfunction "CLK_4") (pintype "bidirectional"))
      (node (ref "U6") (pin "2") (pinfunction "NC1_2") (pintype "bidirectional"))
    )
    (net (code "46") (name "Net-(U4-CMD)") (class "Default")
      (node (ref "U4") (pin "5") (pinfunction "CMD_5") (pintype "bidirectional"))
      (node (ref "U6") (pin "1") (pinfunction "NC2_1") (pintype "bidirectional"))
    )
    (net (code "47") (name "Net-(U4-DAT0)") (class "Default")
      (node (ref "U4") (pin "3") (pinfunction "DAT0_3") (pintype "bidirectional"))
      (node (ref "U6") (pin "23") (pinfunction "NC3_23") (pintype "bidirectional"))
    )
    (net (code "48") (name "Net-(U4-DAT1)") (class "Default")
      (node (ref "U4") (pin "2") (pinfunction "DAT1_2") (pintype "bidirectional"))
      (node (ref "U6") (pin "21") (pinfunction "NC4_21") (pintype "bidirectional"))
    )
    (net (code "49") (name "Net-(U4-DAT2)") (class "Default")
      (node (ref "U4") (pin "7") (pinfunction "DAT2_7") (pintype "bidirectional"))
      (node (ref "U6") (pin "19") (pinfunction "NC5_19") (pintype "bidirectional"))
    )
    (net (code "50") (name "Net-(U4-DAT3)") (class "Default")
      (node (ref "U4") (pin "6") (pinfunction "DAT3_6") (pintype "bidirectional"))
      (node (ref "U6") (pin "22") (pinfunction "NC6_22") (pintype "bidirectional"))
    )
    (net (code "51") (name "Net-(U4-DN)") (class "Default")
      (node (ref "CN1") (pin "A7") (pinfunction "D-_A7") (pintype "bidirectional"))
      (node (ref "CN1") (pin "B7") (pinfunction "D-_B7") (pintype "bidirectional"))
      (node (ref "U4") (pin "16") (pinfunction "DN_16") (pintype "bidirectional"))
    )
    (net (code "52") (name "Net-(U4-DP)") (class "Default")
      (node (ref "CN1") (pin "A6") (pinfunction "D+_A6") (pintype "bidirectional"))
      (node (ref "CN1") (pin "B6") (pinfunction "D+_B6") (pintype "bidirectional"))
      (node (ref "U4") (pin "15") (pinfunction "DP_15") (pintype "bidirectional"))
    )
    (net (code "53") (name "Net-(U4-GPIO)") (class "Default")
      (node (ref "R11") (pin "2") (pinfunction "2_2") (pintype "passive"))
      (node (ref "R12") (pin "2") (pinfunction "2_2") (pintype "passive"))
      (node (ref "U4") (pin "11") (pinfunction "GPIO_11") (pintype "bidirectional"))
    )
    (net (code "54") (name "Net-(U4-PMOS)") (class "Default")
      (node (ref "C6") (pin "2") (pinfunction "2_2") (pintype "passive"))
      (node (ref "U4") (pin "8") (pinfunction "PMOS_8") (pintype "bidirectional"))
    )
    (net (code "55") (name "Net-(U4-VDD)") (class "Default")
      (node (ref "C10") (pin "2") (pinfunction "2_2") (pintype "passive"))
      (node (ref "C11") (pin "2") (pinfunction "2_2") (pintype "passive"))
      (node (ref "R11") (pin "1") (pinfunction "1_1") (pintype "passive"))
      (node (ref "R14") (pin "1") (pinfunction "1_1") (pintype "passive"))
      (node (ref "U4") (pin "13") (pinfunction "VDDA_13") (pintype "bidirectional"))
      (node (ref "U4") (pin "9") (pinfunction "VDD_9") (pintype "bidirectional"))
    )
    (net (code "56") (name "Net-(U8-VBAT)") (class "Default")
      (node (ref "CN5") (pin "+") (pinfunction "+_+") (pintype "passive"))
      (node (ref "U8") (pin "14") (pinfunction "VBAT_14") (pintype "power_in"))
    )
    (net (code "57") (name "SPI_DISPLAY_SCLK") (class "Default")
      (node (ref "CN7") (pin "3") (pinfunction "SCLK_3") (pintype "bidirectional"))
      (node (ref "U2") (pin "10") (pinfunction "P5.3/UCB1CLK/TA3.0/A10_10") (pintype "bidirectional"))
    )
    (net (code "58") (name "SPI_DISPLAY_SIMO") (class "Default")
      (node (ref "CN7") (pin "4") (pinfunction "MOSI_4") (pintype "bidirectional"))
      (node (ref "U2") (pin "9") (pinfunction "P4.4/UCB1SIMO/UCB1SDA/TB0.6/A9_9") (pintype "bidirectional"))
    )
    (net (code "59") (name "UART_DATALOGGER_RX") (class "Default")
      (node (ref "U2") (pin "29") (pinfunction "P2.5/UCA1RXD/UCA1SOMI_29") (pintype "bidirectional"))
      (node (ref "U5") (pin "4") (pinfunction "OUT_4") (pintype "bidirectional"))
    )
    (net (code "60") (name "VUSB") (class "Default")
      (node (ref "C4") (pin "2") (pinfunction "2_2") (pintype "passive"))
      (node (ref "C5") (pin "2") (pinfunction "2_2") (pintype "passive"))
      (node (ref "CN1") (pin "VBUS1") (pinfunction "VBUS_VBUS1") (pintype "bidirectional"))
      (node (ref "CN1") (pin "VBUS2") (pinfunction "VBUS_VBUS2") (pintype "bidirectional"))
      (node (ref "R1") (pin "2") (pinfunction "2_2") (pintype "passive"))
      (node (ref "R8") (pin "1") (pinfunction "1_1") (pintype "passive"))
      (node (ref "R9") (pin "2") (pinfunction "2_2") (pintype "passive"))
      (node (ref "U1") (pin "4") (pinfunction "VDD_4") (pintype "power_in"))
      (node (ref "U4") (pin "10") (pinfunction "5V_10") (pintype "bidirectional"))
    )
    (net (code "61") (name "unconnected-(CN4-Pad7)") (class "Default")
      (node (ref "CN4") (pin "7") (pinfunction "7_7") (pintype "bidirectional"))
    )
    (net (code "62") (name "unconnected-(CN4-TDI-Pad8)") (class "Default")
      (node (ref "CN4") (pin "8") (pinfunction "TDI_8") (pintype "bidirectional"))
    )
    (net (code "63") (name "unconnected-(CN4-TMS-Pad2)") (class "Default")
      (node (ref "CN4") (pin "2") (pinfunction "TMS_2") (pintype "bidirectional"))
    )
    (net (code "64") (name "unconnected-(CN4-~{RST}-Pad10)") (class "Default")
      (node (ref "CN4") (pin "10") (pinfunction "~{RST}_10") (pintype "bidirectional"))
    )
    (net (code "65") (name "unconnected-(U2-DNC-Pad31)") (class "Default")
      (node (ref "U2") (pin "31") (pinfunction "DNC_31") (pintype "bidirectional"))
    )
    (net (code "66") (name "unconnected-(U2-P1.1{slash}UCB0CLK{slash}TA0.1{slash}COMP0.0{slash}A1-Pad13)") (class "Default")
      (node (ref "U2") (pin "13") (pinfunction "P1.1/UCB0CLK/TA0.1/COMP0.0/A1_13") (pintype "bidirectional"))
    )
    (net (code "67") (name "unconnected-(U2-P2.2{slash}ACLK{slash}COMP0.1-Pad16)") (class "Default")
      (node (ref "U2") (pin "16") (pinfunction "P2.2/ACLK/COMP0.1_16") (pintype "bidirectional"))
    )
    (net (code "68") (name "unconnected-(U2-P2.3{slash}TA2.0-Pad25)") (class "Default")
      (node (ref "U2") (pin "25") (pinfunction "P2.3/TA2.0_25") (pintype "bidirectional"))
    )
    (net (code "69") (name "unconnected-(U2-P2.4{slash}UCA1CLK-Pad28)") (class "Default")
      (node (ref "U2") (pin "28") (pinfunction "P2.4/UCA1CLK_28") (pintype "bidirectional"))
    )
    (net (code "70") (name "unconnected-(U2-P2.6{slash}UCA1TXD{slash}UCA1SIMO-Pad30)") (class "Default")
      (node (ref "U2") (pin "30") (pinfunction "P2.6/UCA1TXD/UCA1SIMO_30") (pintype "bidirectional"))
    )
    (net (code "71") (name "unconnected-(U2-P2.7{slash}UCB1STE-Pad36)") (class "Default")
      (node (ref "U2") (pin "36") (pinfunction "P2.7/UCB1STE_36") (pintype "bidirectional"))
    )
    (net (code "72") (name "unconnected-(U2-P3.0{slash}TA2.2-Pad23)") (class "Default")
      (node (ref "U2") (pin "23") (pinfunction "P3.0/TA2.2_23") (pintype "bidirectional"))
    )
    (net (code "73") (name "unconnected-(U2-P3.1{slash}UCA1STE-Pad27)") (class "Default")
      (node (ref "U2") (pin "27") (pinfunction "P3.1/UCA1STE_27") (pintype "bidirectional"))
    )
    (net (code "74") (name "unconnected-(U2-P3.2{slash}UCB1SIMO{slash}UCB1SDA-Pad38)") (class "Default")
      (node (ref "U2") (pin "38") (pinfunction "P3.2/UCB1SIMO/UCB1SDA_38") (pintype "bidirectional"))
    )
    (net (code "75") (name "unconnected-(U2-P3.3{slash}TA2.1-Pad24)") (class "Default")
      (node (ref "U2") (pin "24") (pinfunction "P3.3/TA2.1_24") (pintype "bidirectional"))
    )
    (net (code "76") (name "unconnected-(U2-P3.4{slash}TA2CLK{slash}COMP0OUT-Pad26)") (class "Default")
      (node (ref "U2") (pin "26") (pinfunction "P3.4/TA2CLK/COMP0OUT_26") (pintype "bidirectional"))
    )
    (net (code "77") (name "unconnected-(U2-P3.5{slash}UCB1CLK{slash}TB0TRG-Pad37)") (class "Default")
      (node (ref "U2") (pin "37") (pinfunction "P3.5/UCB1CLK/TB0TRG_37") (pintype "bidirectional"))
    )
    (net (code "78") (name "unconnected-(U2-P3.6{slash}UCB1SOMI{slash}UCB1SCL-Pad39)") (class "Default")
      (node (ref "U2") (pin "39") (pinfunction "P3.6/UCB1SOMI/UCB1SCL_39") (pintype "bidirectional"))
    )
    (net (code "79") (name "unconnected-(U2-P4.3{slash}UCB1SOMI{slash}UCB1SCL{slash}TB0.5{slash}A8-Pad8)") (class "Default")
      (node (ref "U2") (pin "8") (pinfunction "P4.3/UCB1SOMI/UCB1SCL/TB0.5/A8_8") (pintype "bidirectional"))
    )
    (net (code "80") (name "unconnected-(U2-P5.0{slash}UCA0CLK{slash}TB0.2-Pad43)") (class "Default")
      (node (ref "U2") (pin "43") (pinfunction "P5.0/UCA0CLK/TB0.2_43") (pintype "bidirectional"))
    )
    (net (code "81") (name "unconnected-(U2-P5.1{slash}UCA0RXD{slash}UCA0SOMI{slash}TB0.3-Pad44)") (class "Default")
      (node (ref "U2") (pin "44") (pinfunction "P5.1/UCA0RXD/UCA0SOMI/TB0.3_44") (pintype "bidirectional"))
    )
    (net (code "82") (name "unconnected-(U2-P5.2{slash}UCA0TXD{slash}UCA0SIMO{slash}TB0.4-Pad45)") (class "Default")
      (node (ref "U2") (pin "45") (pinfunction "P5.2/UCA0TXD/UCA0SIMO/TB0.4_45") (pintype "bidirectional"))
    )
    (net (code "83") (name "unconnected-(U2-P5.5{slash}UCB0CLK{slash}TA2CLK-Pad19)") (class "Default")
      (node (ref "U2") (pin "19") (pinfunction "P5.5/UCB0CLK/TA2CLK_19") (pintype "bidirectional"))
    )
    (net (code "84") (name "unconnected-(U2-P5.6{slash}UCB0STE{slash}TA2.0-Pad20)") (class "Default")
      (node (ref "U2") (pin "20") (pinfunction "P5.6/UCB0STE/TA2.0_20") (pintype "bidirectional"))
    )
    (net (code "85") (name "unconnected-(U2-P5.7{slash}TA2.1{slash}COMP0.2-Pad21)") (class "Default")
      (node (ref "U2") (pin "21") (pinfunction "P5.7/TA2.1/COMP0.2_21") (pintype "bidirectional"))
    )
    (net (code "86") (name "unconnected-(U2-P6.0{slash}TA2.2{slash}COMP0.3-Pad22)") (class "Default")
      (node (ref "U2") (pin "22") (pinfunction "P6.0/TA2.2/COMP0.3_22") (pintype "bidirectional"))
    )
    (net (code "87") (name "unconnected-(U2-P6.1{slash}TB0CLK-Pad40)") (class "Default")
      (node (ref "U2") (pin "40") (pinfunction "P6.1/TB0CLK_40") (pintype "bidirectional"))
    )
    (net (code "88") (name "unconnected-(U3-DP-Pad4)") (class "Default")
      (node (ref "U3") (pin "4") (pinfunction "DP_4") (pintype "bidirectional"))
    )
    (net (code "89") (name "unconnected-(U6-NO4-Pad17)") (class "Default")
      (node (ref "U6") (pin "17") (pinfunction "NO4_17") (pintype "bidirectional"))
    )
    (net (code "90") (name "unconnected-(U6-NO5-Pad18)") (class "Default")
      (node (ref "U6") (pin "18") (pinfunction "NO5_18") (pintype "bidirectional"))
    )
    (net (code "91") (name "unconnected-(U8-32KHZ-Pad1)") (class "Default")
      (node (ref "U8") (pin "1") (pinfunction "32KHZ_1") (pintype "output"))
    )
    (net (code "92") (name "unconnected-(U8-~{INT}{slash}SQW-Pad3)") (class "Default")
      (node (ref "U8") (pin "3") (pinfunction "~{INT}/SQW_3") (pintype "output"))
    )
    (net (code "93") (name "unconnected-(U8-~{RST}-Pad4)") (class "Default")
      (node (ref "U8") (pin "4") (pinfunction "~{RST}_4") (pintype "passive"))
    )
  )
)
